# VCSEL.net
KiCad netlist of a schematic drawn in Altium Designer
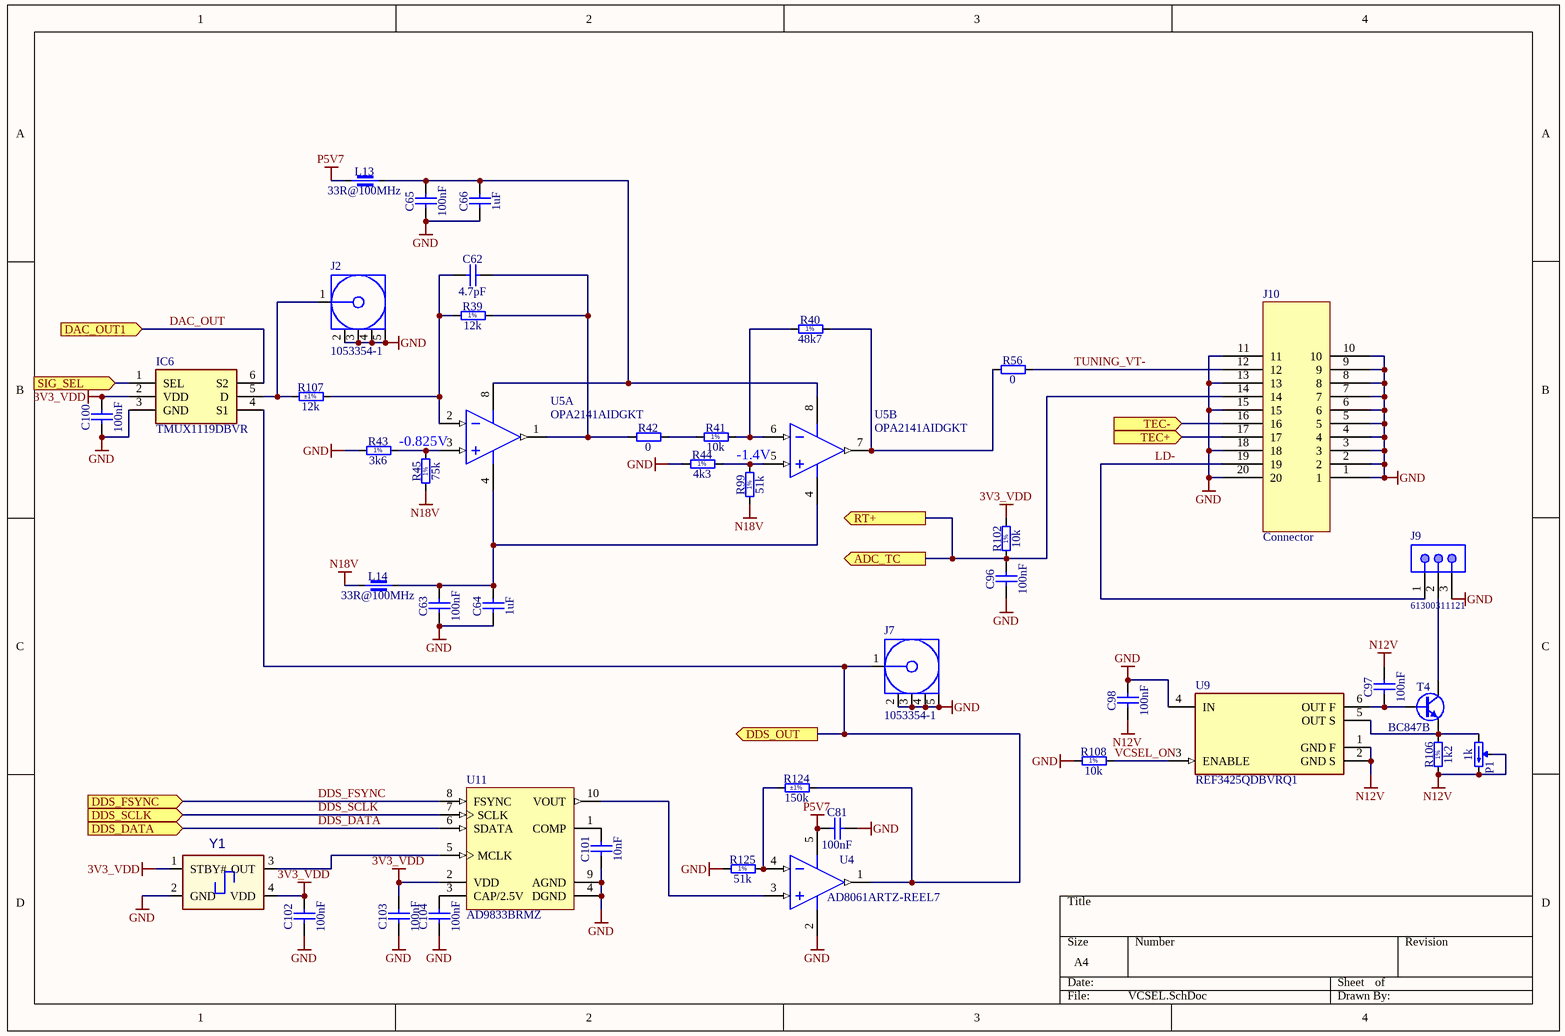
[diagram p0: VCSEL.SchDoc]

(export (version "E")
  (design (tool "Eeschema 10.0.6"))
  (components
    (comp (ref "C62")
      (value "4.7pF")
      (footprint "CAPC1005X70N")
      (description "Non-polarised capacitor")
      (fields
        (field (name "PART NUMBER") "CC0402_4.7PF_50V_0.25PF_C0G_VISHAY_VJ_NON-MAGNETIC")
        (field (name "VOLTAGE") "50V")
        (field (name "AUTHOR") "CERN DEM MR")
      )
      (libsource (lib "Capacitors") (part "Capacitor - non polarized"))
    )
    (comp (ref "C63")
      (value "100nF")
      (footprint "CAPC1608X87N")
      (description "Non-polarised capacitor")
      (fields
        (field (name "PART NUMBER") "CC0603_100NF_50V_10%_X5R")
        (field (name "VOLTAGE") "50V")
        (field (name "AUTHOR") "CERN DEM MR")
      )
      (libsource (lib "Capacitors") (part "Capacitor - non polarized"))
    )
    (comp (ref "C64")
      (value "1uF")
      (footprint "CAPC1608X87N")
      (description "Non-polarised capacitor")
      (fields
        (field (name "PART NUMBER") "CC0603_1UF_25V_10%_X7R")
        (field (name "VOLTAGE") "25V")
        (field (name "AUTHOR") "CERN DEM JLC")
      )
      (libsource (lib "Capacitors") (part "Capacitor - non polarized"))
    )
    (comp (ref "C65")
      (value "100nF")
      (footprint "CAPC1005X55N")
      (description "Non-polarised capacitor")
      (fields
        (field (name "PART NUMBER") "CC0402_100NF_16V_10%_X7R")
        (field (name "VOLTAGE") "16V")
        (field (name "AUTHOR") "CERN DEM JLC")
      )
      (libsource (lib "Capacitors") (part "Capacitor - non polarized"))
    )
    (comp (ref "C66")
      (value "1uF")
      (footprint "CAPC1005X55N")
      (description "Non-polarised capacitor")
      (fields
        (field (name "PART NUMBER") "CC0402_1UF_16V_10%_X5R")
        (field (name "VOLTAGE") "16V")
        (field (name "AUTHOR") "CERN DEM JLC")
      )
      (libsource (lib "Capacitors") (part "Capacitor - non polarized"))
    )
    (comp (ref "C81")
      (value "100nF")
      (footprint "CAPC1005X55N")
      (description "Non-polarised capacitor")
      (fields
        (field (name "PART NUMBER") "CC0402_100NF_16V_10%_X7R")
        (field (name "VOLTAGE") "16V")
        (field (name "AUTHOR") "CERN DEM JLC")
      )
      (libsource (lib "Capacitors") (part "Capacitor - non polarized"))
    )
    (comp (ref "C96")
      (value "100nF")
      (footprint "CAPC1005X55N")
      (description "Non-polarised capacitor")
      (fields
        (field (name "PART NUMBER") "CC0402_100NF_16V_10%_X7R")
        (field (name "VOLTAGE") "16V")
        (field (name "AUTHOR") "CERN DEM JLC")
      )
      (libsource (lib "Capacitors") (part "Capacitor - non polarized"))
    )
    (comp (ref "C97")
      (value "100nF")
      (footprint "CAPC1005X55N")
      (description "Non-polarised capacitor")
      (fields
        (field (name "PART NUMBER") "CC0402_100NF_16V_10%_X7R")
        (field (name "VOLTAGE") "16V")
        (field (name "AUTHOR") "CERN DEM JLC")
      )
      (libsource (lib "Capacitors") (part "Capacitor - non polarized"))
    )
    (comp (ref "C98")
      (value "100nF")
      (footprint "CAPC1005X55N")
      (description "Non-polarised capacitor")
      (fields
        (field (name "PART NUMBER") "CC0402_100NF_16V_10%_X7R")
        (field (name "VOLTAGE") "16V")
        (field (name "AUTHOR") "CERN DEM JLC")
      )
      (libsource (lib "Capacitors") (part "Capacitor - non polarized"))
    )
    (comp (ref "C100")
      (value "100nF")
      (footprint "CAPC1005X55N")
      (description "Non-polarised capacitor")
      (fields
        (field (name "PART NUMBER") "CC0402_100NF_16V_10%_X7R")
        (field (name "VOLTAGE") "16V")
        (field (name "AUTHOR") "CERN DEM JLC")
      )
      (libsource (lib "Capacitors") (part "Capacitor - non polarized"))
    )
    (comp (ref "C101")
      (value "10nF")
      (footprint "CAPC1005X55N")
      (description "Non-polarised capacitor")
      (fields
        (field (name "PART NUMBER") "CC0402_10NF_16V_10%_X7R")
        (field (name "VOLTAGE") "16V")
        (field (name "AUTHOR") "CERN DEM JLC")
      )
      (libsource (lib "Capacitors") (part "Capacitor - non polarized"))
    )
    (comp (ref "C102")
      (value "100nF")
      (footprint "CAPC1005X55N")
      (description "Non-polarised capacitor")
      (fields
        (field (name "PART NUMBER") "CC0402_100NF_16V_10%_X7R")
        (field (name "VOLTAGE") "16V")
        (field (name "AUTHOR") "CERN DEM JLC")
      )
      (libsource (lib "Capacitors") (part "Capacitor - non polarized"))
    )
    (comp (ref "C103")
      (value "100nF")
      (footprint "CAPC1005X55N")
      (description "Non-polarised capacitor")
      (fields
        (field (name "PART NUMBER") "CC0402_100NF_16V_10%_X7R")
        (field (name "VOLTAGE") "16V")
        (field (name "AUTHOR") "CERN DEM JLC")
      )
      (libsource (lib "Capacitors") (part "Capacitor - non polarized"))
    )
    (comp (ref "C104")
      (value "100nF")
      (footprint "CAPC1005X55N")
      (description "Non-polarised capacitor")
      (fields
        (field (name "PART NUMBER") "CC0402_100NF_16V_10%_X7R")
        (field (name "VOLTAGE") "16V")
        (field (name "AUTHOR") "CERN DEM JLC")
      )
      (libsource (lib "Capacitors") (part "Capacitor - non polarized"))
    )
    (comp (ref "IC6")
      (value "TMUX1119DBVR")
      (footprint "SamacSys:SOT95P280X145-6N")
      (description "Integrated Circuit")
      (libsource (lib "*") (part "TMUX1119DBVR"))
    )
    (comp (ref "J2")
      (value "1053354-1")
      (footprint "TECO-1053354-1_V")
      (description "Female Coaxial Connector, Pitch 2.55 mm, Height 9.5 mm, Tail Length 3.9 mm, RoHS, Bulk")
      (fields (field (name "MANUFACTURER") "TE Connectivity"))
      (libsource (lib "Altium Content Vault") (part "CN-S-4F-RF5"))
    )
    (comp (ref "J7")
      (value "1053354-1")
      (footprint "TECO-1053354-1_V")
      (description "Female Coaxial Connector, Pitch 2.55 mm, Height 9.5 mm, Tail Length 3.9 mm, RoHS, Bulk")
      (fields (field (name "MANUFACTURER") "TE Connectivity"))
      (libsource (lib "Altium Content Vault") (part "CN-S-4F-RF5"))
    )
    (comp (ref "J9")
      (value "61300311121")
      (footprint "61300311121")
      (description "WR-PHD Pin Header, THT, pitch 2.54mm, Single Row, Vertical, 3pin")
      (fields (field (name "PUBLISHER") "Wurth Elektronik"))
      (libsource (lib "ALTIUM-WR-PHD_PIN_HEADER_SOCKET_HEADER-rev19a") (part "61300311121"))
    )
    (comp (ref "J10")
      (value "Connector")
      (footprint "VCSEL_CONNECTOR")
      (description "VCSEL connector")
      (libsource (lib "VCSEL_Driver_Lib") (part "VCSEL_CONNECTOR"))
    )
    (comp (ref "L13")
      (value "33R@100MHz")
      (footprint "INDC1005X55N")
      (fields
        (field (name "PART NUMBER") "IND0402_MURATA_BLM15PX330SN1D")
        (field (name "POWER") "3A")
        (field (name "TOLERANCE") "±25%")
        (field (name "AUTHOR") "CERN DEM JMW")
      )
      (libsource (lib "Inductors & Transformers") (part "Ferrite Bead"))
    )
    (comp (ref "L14")
      (value "33R@100MHz")
      (footprint "INDC1005X55N")
      (fields
        (field (name "PART NUMBER") "IND0402_MURATA_BLM15PX330SN1D")
        (field (name "POWER") "3A")
        (field (name "TOLERANCE") "±25%")
        (field (name "AUTHOR") "CERN DEM JMW")
      )
      (libsource (lib "Inductors & Transformers") (part "Ferrite Bead"))
    )
    (comp (ref "P1")
      (value "1k")
      (footprint "TRIM_BOURNS_3266W")
      (description "Trimming Potentiometer")
      (fields
        (field (name "PART NUMBER") "TRIM_12T_1K_BOURNS_3266W-1-102LF")
        (field (name "POWER") "0.25W")
        (field (name "AUTHOR") "CERN DEM JLC")
      )
      (libsource (lib "Resistors") (part "Trimming Potentiometer"))
    )
    (comp (ref "R39")
      (value "12k")
      (footprint "RESC1005X40N")
      (description "Resistor - 1%")
      (fields
        (field (name "PART NUMBER") "R0402_12K_1%_0.0625W_100PPM")
        (field (name "POWER") "0.0625W")
        (field (name "AUTHOR") "CERN DEM JLC")
      )
      (libsource (lib "Resistors") (part "Resistor - 1%"))
    )
    (comp (ref "R40")
      (value "48k7")
      (footprint "RESC1608X55N")
      (description "Resistor - 1%")
      (fields
        (field (name "PART NUMBER") "R0603_48K7_1%_0.1W_100PPM")
        (field (name "POWER") "0.1W")
        (field (name "AUTHOR") "CERN DEM JLC")
      )
      (libsource (lib "Resistors") (part "Resistor - 1%"))
    )
    (comp (ref "R41")
      (value "10k")
      (footprint "RESC1005X40N")
      (description "Resistor - 1%")
      (fields
        (field (name "PART NUMBER") "R0402_10K_1%_0.0625W_100PPM")
        (field (name "POWER") "0.0625W")
        (field (name "AUTHOR") "CERN DEM JLC")
      )
      (libsource (lib "Resistors") (part "Resistor - 1%"))
    )
    (comp (ref "R42")
      (value "0")
      (footprint "RESC1005X40N")
      (description "Resistor")
      (fields
        (field (name "PART NUMBER") "R0402_0R_JUMPER")
        (field (name "MANUFACTURER") "GENERIC")
        (field (name "AUTHOR") "CERN DEM JLC")
      )
      (libsource (lib "Resistors") (part "Resistor"))
    )
    (comp (ref "R43")
      (value "3k6")
      (footprint "RESC1005X40N")
      (description "Resistor - 1%")
      (fields
        (field (name "PART NUMBER") "R0402_3K6_1%_0.0625W_100PPM")
        (field (name "POWER") "0.0625W")
        (field (name "AUTHOR") "CERN DEM JLC")
      )
      (libsource (lib "Resistors") (part "Resistor - 1%"))
    )
    (comp (ref "R44")
      (value "4k3")
      (footprint "RESC1005X40N")
      (description "Resistor - 1%")
      (fields
        (field (name "PART NUMBER") "R0402_4K3_1%_0.0625W_100PPM")
        (field (name "POWER") "0.0625W")
        (field (name "AUTHOR") "CERN DEM JLC")
      )
      (libsource (lib "Resistors") (part "Resistor - 1%"))
    )
    (comp (ref "R45")
      (value "75k")
      (footprint "RESC1005X40N")
      (description "Resistor - 1%")
      (fields
        (field (name "PART NUMBER") "R0402_75K_1%_0.0625W_100PPM")
        (field (name "POWER") "0.0625W")
        (field (name "AUTHOR") "CERN DEM JLC")
      )
      (libsource (lib "Resistors") (part "Resistor - 1%"))
    )
    (comp (ref "R56")
      (value "0")
      (footprint "RESC1005X40N")
      (description "Resistor")
      (fields
        (field (name "PART NUMBER") "R0402_0R_JUMPER")
        (field (name "MANUFACTURER") "GENERIC")
        (field (name "AUTHOR") "CERN DEM JLC")
      )
      (libsource (lib "Resistors") (part "Resistor"))
    )
    (comp (ref "R99")
      (value "51k")
      (footprint "RESC1005X40N")
      (description "Resistor - 1%")
      (fields
        (field (name "PART NUMBER") "R0402_51K_1%_0.0625W_100PPM")
        (field (name "POWER") "0.0625W")
        (field (name "AUTHOR") "CERN DEM JLC")
      )
      (libsource (lib "Resistors") (part "Resistor - 1%"))
    )
    (comp (ref "R102")
      (value "10k")
      (footprint "RESC1005X40N")
      (description "Resistor - 1%")
      (fields
        (field (name "PART NUMBER") "R0402_10K_1%_0.0625W_100PPM")
        (field (name "POWER") "0.0625W")
        (field (name "AUTHOR") "CERN DEM JLC")
      )
      (libsource (lib "Resistors") (part "Resistor - 1%"))
    )
    (comp (ref "R106")
      (value "1k2")
      (footprint "RESC1005X40N")
      (description "Resistor - 1%")
      (fields
        (field (name "PART NUMBER") "R0402_1K2_1%_0.0625W_100PPM")
        (field (name "POWER") "0.0625W")
        (field (name "AUTHOR") "CERN DEM JLC")
      )
      (libsource (lib "Resistors") (part "Resistor - 1%"))
    )
    (comp (ref "R107")
      (value "12k")
      (footprint "RESC1005X40N")
      (description "Resistor - 1%")
      (fields
        (field (name "PART NUMBER") "R0402_12K_1%_0.0625W_100PPM")
        (field (name "MANUFACTURER") "GENERIC")
        (field (name "TOLERANCE") "±1%")
        (field (name "AUTHOR") "CERN DEM JLC")
      )
      (libsource (lib "Resistors") (part "Resistor - 1%"))
    )
    (comp (ref "R108")
      (value "10k")
      (footprint "RESC1005X40N")
      (description "Resistor - 1%")
      (fields
        (field (name "PART NUMBER") "R0402_10K_1%_0.0625W_100PPM")
        (field (name "POWER") "0.0625W")
        (field (name "AUTHOR") "CERN DEM JLC")
      )
      (libsource (lib "Resistors") (part "Resistor - 1%"))
    )
    (comp (ref "R124")
      (value "150k")
      (footprint "RESC1005X40N")
      (description "Resistor - 1%")
      (fields
        (field (name "TOLERANCE") "±1%")
        (field (name "PART NUMBER") "R0402_150K_1%_0.0625W_100PPM")
        (field (name "POWER") "0.0625W")
        (field (name "AUTHOR") "CERN DEM JLC")
      )
      (libsource (lib "Resistors") (part "Resistor - 1%"))
    )
    (comp (ref "R125")
      (value "51k")
      (footprint "RESC1005X40N")
      (description "Resistor - 1%")
      (fields
        (field (name "PART NUMBER") "R0402_51K_1%_0.0625W_100PPM")
        (field (name "POWER") "0.0625W")
        (field (name "AUTHOR") "CERN DEM JLC")
      )
      (libsource (lib "Resistors") (part "Resistor - 1%"))
    )
    (comp (ref "T4")
      (value "BC847B")
      (footprint "SOT95P230X110-3N")
      (description "NPN Transistor")
      (fields (field (name "MANUFACTURER") "NXP SEMICONDUCTORS") (field (name "AUTHOR") "CERN DEM JLC"))
      (libsource (lib "ICs And Semiconductors") (part "NPN B1 E2 C3"))
    )
    (comp (ref "U4")
      (value "AD8061ARTZ-REEL7")
      (footprint "ADI-RJ-5_L")
      (fields (field (name "GENERIC PART NUMBER") "AD8061") (field (name "MANUFACTURER") "Analog Devices"))
      (libsource (lib "Altium Content Vault") (part "ADI-AD80XX-5"))
    )
    (comp (ref "U5")
      (value "OPA2141AIDGKT")
      (footprint "DGK0008A_M")
      (fields (field (name "MANUFACTURER") "Texas Instruments"))
      (libsource (lib "Altium Content Vault") (part "TI-OPA-8_2"))
    )
    (comp (ref "U9")
      (value "REF3425QDBVRQ1")
      (footprint "FP-DBV0006A-MFG")
      (description "IC VREF SERIES 0.05% SOT23-6")
      (fields
        (field (name "OCTOPART") "https://octopart.com/ref3433qdbvrq1-texas+instruments-95842010")
        (field (name "MANUFACTURER") "Texas Instruments")
      )
      (libsource (lib "Altium Content Vault") (part "852d3c1243c2caefb114a4c8e829102"))
    )
    (comp (ref "U11")
      (value "AD9833BRMZ")
      (footprint "ADI-RM-10_M")
      (libsource (lib "Altium Content Vault") (part "ADI-AD9833-RM-10"))
    )
    (comp (ref "Y1")
      (value "OSCILLATOR_4P_nSTBY")
      (footprint "OSCILLATOR_CDFN_L2.5W2.0H0.85")
      (fields (field (name "OWNER") "Sam Charles"))
      (libsource (lib "MCHP-CDB") (part "OSCILLATOR_4P_nSTBY"))
    )
  )
  (nets
    (net (code "1") (name "/ADC_TC") (class "Default")
      (node (ref "C96") (pin "2") (pinfunction "2_2") (pintype "passive"))
      (node (ref "J10") (pin "14") (pinfunction "14_14") (pintype "passive"))
      (node (ref "R102") (pin "1") (pinfunction "1_1") (pintype "passive"))
    )
    (net (code "2") (name "/DAC_OUT") (class "Default")
      (node (ref "IC6") (pin "6") (pinfunction "S2_6") (pintype "passive"))
    )
    (net (code "3") (name "/DDS_DATA") (class "Default")
      (node (ref "U11") (pin "6") (pinfunction "SDATA_6") (pintype "input"))
    )
    (net (code "4") (name "/DDS_FSYNC") (class "Default")
      (node (ref "U11") (pin "8") (pinfunction "FSYNC_8") (pintype "input"))
    )
    (net (code "5") (name "/DDS_OUT") (class "Default")
      (node (ref "IC6") (pin "4") (pinfunction "S1_4") (pintype "passive"))
      (node (ref "J7") (pin "1") (pinfunction "1_1") (pintype "passive"))
      (node (ref "R124") (pin "2") (pinfunction "2_2") (pintype "passive"))
      (node (ref "U4") (pin "1") (pinfunction "VOUT_1") (pintype "output"))
    )
    (net (code "6") (name "/DDS_SCLK") (class "Default")
      (node (ref "U11") (pin "7") (pinfunction "SCLK_7") (pintype "input"))
    )
    (net (code "7") (name "/LD-") (class "Default")
      (node (ref "J10") (pin "19") (pinfunction "19_19") (pintype "passive"))
      (node (ref "J9") (pin "1") (pinfunction "1_1") (pintype "passive"))
    )
    (net (code "8") (name "/SIG_SEL") (class "Default")
      (node (ref "IC6") (pin "1") (pinfunction "SEL_1") (pintype "passive"))
    )
    (net (code "9") (name "/TEC+") (class "Default")
      (node (ref "J10") (pin "17") (pinfunction "17_17") (pintype "passive"))
    )
    (net (code "10") (name "/TEC-") (class "Default")
      (node (ref "J10") (pin "16") (pinfunction "16_16") (pintype "passive"))
    )
    (net (code "11") (name "/TUNING_VT-") (class "Default")
      (node (ref "J10") (pin "12") (pinfunction "12_12") (pintype "passive"))
      (node (ref "R56") (pin "2") (pinfunction "2_2") (pintype "passive"))
    )
    (net (code "12") (name "/VCSEL_ON") (class "Default")
      (node (ref "R108") (pin "2") (pinfunction "2_2") (pintype "passive"))
      (node (ref "U9") (pin "3") (pinfunction "ENABLE_3") (pintype "input"))
    )
    (net (code "13") (name "3V3_VDD") (class "Default")
      (node (ref "C100") (pin "2") (pinfunction "2_2") (pintype "passive"))
      (node (ref "C102") (pin "2") (pinfunction "2_2") (pintype "passive"))
      (node (ref "C103") (pin "2") (pinfunction "2_2") (pintype "passive"))
      (node (ref "IC6") (pin "2") (pinfunction "VDD_2") (pintype "passive"))
      (node (ref "R102") (pin "2") (pinfunction "2_2") (pintype "passive"))
      (node (ref "U11") (pin "2") (pinfunction "VDD_2") (pintype "power_in"))
      (node (ref "Y1") (pin "1") (pinfunction "STBY#_1") (pintype "passive"))
      (node (ref "Y1") (pin "4") (pinfunction "VDD_4") (pintype "passive"))
    )
    (net (code "14") (name "GND") (class "Default")
      (node (ref "C100") (pin "1") (pinfunction "1_1") (pintype "passive"))
      (node (ref "C101") (pin "1") (pinfunction "1_1") (pintype "passive"))
      (node (ref "C102") (pin "1") (pinfunction "1_1") (pintype "passive"))
      (node (ref "C103") (pin "1") (pinfunction "1_1") (pintype "passive"))
      (node (ref "C104") (pin "1") (pinfunction "1_1") (pintype "passive"))
      (node (ref "C63") (pin "1") (pinfunction "1_1") (pintype "passive"))
      (node (ref "C64") (pin "1") (pinfunction "1_1") (pintype "passive"))
      (node (ref "C65") (pin "1") (pinfunction "1_1") (pintype "passive"))
      (node (ref "C66") (pin "1") (pinfunction "1_1") (pintype "passive"))
      (node (ref "C81") (pin "2") (pinfunction "2_2") (pintype "passive"))
      (node (ref "C96") (pin "1") (pinfunction "1_1") (pintype "passive"))
      (node (ref "C98") (pin "2") (pinfunction "2_2") (pintype "passive"))
      (node (ref "IC6") (pin "3") (pinfunction "GND_3") (pintype "passive"))
      (node (ref "J10") (pin "1") (pinfunction "1_1") (pintype "passive"))
      (node (ref "J10") (pin "10") (pinfunction "10_10") (pintype "passive"))
      (node (ref "J10") (pin "11") (pinfunction "11_11") (pintype "passive"))
      (node (ref "J10") (pin "13") (pinfunction "13_13") (pintype "passive"))
      (node (ref "J10") (pin "15") (pinfunction "15_15") (pintype "passive"))
      (node (ref "J10") (pin "18") (pinfunction "18_18") (pintype "passive"))
      (node (ref "J10") (pin "2") (pinfunction "2_2") (pintype "passive"))
      (node (ref "J10") (pin "20") (pinfunction "20_20") (pintype "passive"))
      (node (ref "J10") (pin "3") (pinfunction "3_3") (pintype "passive"))
      (node (ref "J10") (pin "4") (pinfunction "4_4") (pintype "passive"))
      (node (ref "J10") (pin "5") (pinfunction "5_5") (pintype "passive"))
      (node (ref "J10") (pin "6") (pinfunction "6_6") (pintype "passive"))
      (node (ref "J10") (pin "7") (pinfunction "7_7") (pintype "passive"))
      (node (ref "J10") (pin "8") (pinfunction "8_8") (pintype "passive"))
      (node (ref "J10") (pin "9") (pinfunction "9_9") (pintype "passive"))
      (node (ref "J2") (pin "2") (pinfunction "2_2") (pintype "passive"))
      (node (ref "J2") (pin "3") (pinfunction "3_3") (pintype "passive"))
      (node (ref "J2") (pin "4") (pinfunction "4_4") (pintype "passive"))
      (node (ref "J2") (pin "5") (pinfunction "5_5") (pintype "passive"))
      (node (ref "J7") (pin "2") (pinfunction "2_2") (pintype "passive"))
      (node (ref "J7") (pin "3") (pinfunction "3_3") (pintype "passive"))
      (node (ref "J7") (pin "4") (pinfunction "4_4") (pintype "passive"))
      (node (ref "J7") (pin "5") (pinfunction "5_5") (pintype "passive"))
      (node (ref "J9") (pin "3") (pinfunction "3_3") (pintype "passive"))
      (node (ref "R108") (pin "1") (pinfunction "1_1") (pintype "passive"))
      (node (ref "R125") (pin "1") (pinfunction "1_1") (pintype "passive"))
      (node (ref "R43") (pin "1") (pinfunction "1_1") (pintype "passive"))
      (node (ref "R44") (pin "1") (pinfunction "1_1") (pintype "passive"))
      (node (ref "U11") (pin "4") (pinfunction "DGND_4") (pintype "power_in"))
      (node (ref "U11") (pin "9") (pinfunction "AGND_9") (pintype "power_in"))
      (node (ref "U4") (pin "2") (pinfunction "-VS_2") (pintype "power_in"))
      (node (ref "U9") (pin "4") (pinfunction "IN_4") (pintype "power_in"))
      (node (ref "Y1") (pin "2") (pinfunction "GND_2") (pintype "passive"))
    )
    (net (code "15") (name "N12V") (class "Default")
      (node (ref "C97") (pin "2") (pinfunction "2_2") (pintype "passive"))
      (node (ref "C98") (pin "1") (pinfunction "1_1") (pintype "passive"))
      (node (ref "P1") (pin "2") (pinfunction "W_2") (pintype "passive"))
      (node (ref "P1") (pin "3") (pinfunction "CW_3") (pintype "passive"))
      (node (ref "R106") (pin "1") (pinfunction "1_1") (pintype "passive"))
      (node (ref "U9") (pin "1") (pinfunction "GND_F_1") (pintype "power_in"))
      (node (ref "U9") (pin "2") (pinfunction "GND_S_2") (pintype "power_in"))
    )
    (net (code "16") (name "N18V") (class "Default")
      (node (ref "L14") (pin "1") (pinfunction "1_1") (pintype "passive"))
      (node (ref "R45") (pin "1") (pinfunction "1_1") (pintype "passive"))
      (node (ref "R99") (pin "1") (pinfunction "1_1") (pintype "passive"))
    )
    (net (code "17") (name "Net-(IC6-D)") (class "Default")
      (node (ref "IC6") (pin "5") (pinfunction "D_5") (pintype "passive"))
      (node (ref "J2") (pin "1") (pinfunction "1_1") (pintype "passive"))
      (node (ref "R107") (pin "1") (pinfunction "1_1") (pintype "passive"))
    )
    (net (code "18") (name "Net-(P1-CCW)") (class "Default")
      (node (ref "P1") (pin "1") (pinfunction "CCW_1") (pintype "passive"))
      (node (ref "R106") (pin "2") (pinfunction "2_2") (pintype "passive"))
      (node (ref "T4") (pin "2") (pinfunction "E_2") (pintype "passive"))
      (node (ref "U9") (pin "5") (pinfunction "OUT_S_5") (pintype "power_in"))
    )
    (net (code "19") (name "Net-(R41-Pad1)") (class "Default")
      (node (ref "R41") (pin "1") (pinfunction "1_1") (pintype "passive"))
      (node (ref "R42") (pin "2") (pinfunction "2_2") (pintype "passive"))
    )
    (net (code "20") (name "Net-(T4-B)") (class "Default")
      (node (ref "C97") (pin "1") (pinfunction "1_1") (pintype "passive"))
      (node (ref "T4") (pin "1") (pinfunction "B_1") (pintype "passive"))
      (node (ref "U9") (pin "6") (pinfunction "OUT_F_6") (pintype "power_in"))
    )
    (net (code "21") (name "Net-(T4-C)") (class "Default")
      (node (ref "J9") (pin "2") (pinfunction "2_2") (pintype "passive"))
      (node (ref "T4") (pin "3") (pinfunction "C_3") (pintype "passive"))
    )
    (net (code "22") (name "Net-(U4--IN)") (class "Default")
      (node (ref "R124") (pin "1") (pinfunction "1_1") (pintype "passive"))
      (node (ref "R125") (pin "2") (pinfunction "2_2") (pintype "passive"))
      (node (ref "U4") (pin "4") (pinfunction "-IN_4") (pintype "input"))
    )
    (net (code "23") (name "Net-(U5A-IN_A+)") (class "Default")
      (node (ref "R43") (pin "2") (pinfunction "2_2") (pintype "passive"))
      (node (ref "R45") (pin "2") (pinfunction "2_2") (pintype "passive"))
      (node (ref "U5") (pin "3") (pinfunction "IN_A+_3") (pintype "input"))
    )
    (net (code "24") (name "Net-(U5A-IN_A-)") (class "Default")
      (node (ref "C62") (pin "1") (pinfunction "1_1") (pintype "passive"))
      (node (ref "R107") (pin "2") (pinfunction "2_2") (pintype "passive"))
      (node (ref "R39") (pin "1") (pinfunction "1_1") (pintype "passive"))
      (node (ref "U5") (pin "2") (pinfunction "IN_A-_2") (pintype "input"))
    )
    (net (code "25") (name "Net-(U5A-OUT_A)") (class "Default")
      (node (ref "C62") (pin "2") (pinfunction "2_2") (pintype "passive"))
      (node (ref "R39") (pin "2") (pinfunction "2_2") (pintype "passive"))
      (node (ref "R42") (pin "1") (pinfunction "1_1") (pintype "passive"))
      (node (ref "U5") (pin "1") (pinfunction "OUT_A_1") (pintype "output"))
    )
    (net (code "26") (name "Net-(U5A-V+)") (class "Default")
      (node (ref "C65") (pin "2") (pinfunction "2_2") (pintype "passive"))
      (node (ref "C66") (pin "2") (pinfunction "2_2") (pintype "passive"))
      (node (ref "L13") (pin "2") (pinfunction "2_2") (pintype "passive"))
      (node (ref "U5") (pin "8") (pinfunction "V+_8") (pintype "power_in"))
    )
    (net (code "27") (name "Net-(U5A-V-)") (class "Default")
      (node (ref "C63") (pin "2") (pinfunction "2_2") (pintype "passive"))
      (node (ref "C64") (pin "2") (pinfunction "2_2") (pintype "passive"))
      (node (ref "L14") (pin "2") (pinfunction "2_2") (pintype "passive"))
      (node (ref "U5") (pin "4") (pinfunction "V-_4") (pintype "power_in"))
    )
    (net (code "28") (name "Net-(U5B-IN_B+)") (class "Default")
      (node (ref "R44") (pin "2") (pinfunction "2_2") (pintype "passive"))
      (node (ref "R99") (pin "2") (pinfunction "2_2") (pintype "passive"))
      (node (ref "U5") (pin "5") (pinfunction "IN_B+_5") (pintype "input"))
    )
    (net (code "29") (name "Net-(U5B-IN_B-)") (class "Default")
      (node (ref "R40") (pin "1") (pinfunction "1_1") (pintype "passive"))
      (node (ref "R41") (pin "2") (pinfunction "2_2") (pintype "passive"))
      (node (ref "U5") (pin "6") (pinfunction "IN_B-_6") (pintype "input"))
    )
    (net (code "30") (name "Net-(U5B-OUT_B)") (class "Default")
      (node (ref "R40") (pin "2") (pinfunction "2_2") (pintype "passive"))
      (node (ref "R56") (pin "1") (pinfunction "1_1") (pintype "passive"))
      (node (ref "U5") (pin "7") (pinfunction "OUT_B_7") (pintype "output"))
    )
    (net (code "31") (name "Net-(U11-CAP{slash}2.5V)") (class "Default")
      (node (ref "C104") (pin "2") (pinfunction "2_2") (pintype "passive"))
      (node (ref "U11") (pin "3") (pinfunction "CAP/2.5V_3") (pintype "power_in"))
    )
    (net (code "32") (name "Net-(U11-COMP)") (class "Default")
      (node (ref "C101") (pin "2") (pinfunction "2_2") (pintype "passive"))
      (node (ref "U11") (pin "1") (pinfunction "COMP_1") (pintype "passive"))
    )
    (net (code "33") (name "Net-(U11-MCLK)") (class "Default")
      (node (ref "U11") (pin "5") (pinfunction "MCLK_5") (pintype "input"))
      (node (ref "Y1") (pin "3") (pinfunction "OUT_3") (pintype "passive"))
    )
    (net (code "34") (name "Net-(U11-VOUT)") (class "Default")
      (node (ref "U11") (pin "10") (pinfunction "VOUT_10") (pintype "output"))
      (node (ref "U4") (pin "3") (pinfunction "+IN_3") (pintype "input"))
    )
    (net (code "35") (name "P5V7") (class "Default")
      (node (ref "C81") (pin "1") (pinfunction "1_1") (pintype "passive"))
      (node (ref "L13") (pin "1") (pinfunction "1_1") (pintype "passive"))
      (node (ref "U4") (pin "5") (pinfunction "+VS_5") (pintype "power_in"))
    )
  )
)
